# Parallel_CS_V4.net
KiCad netlist of a schematic drawn in EAGLE
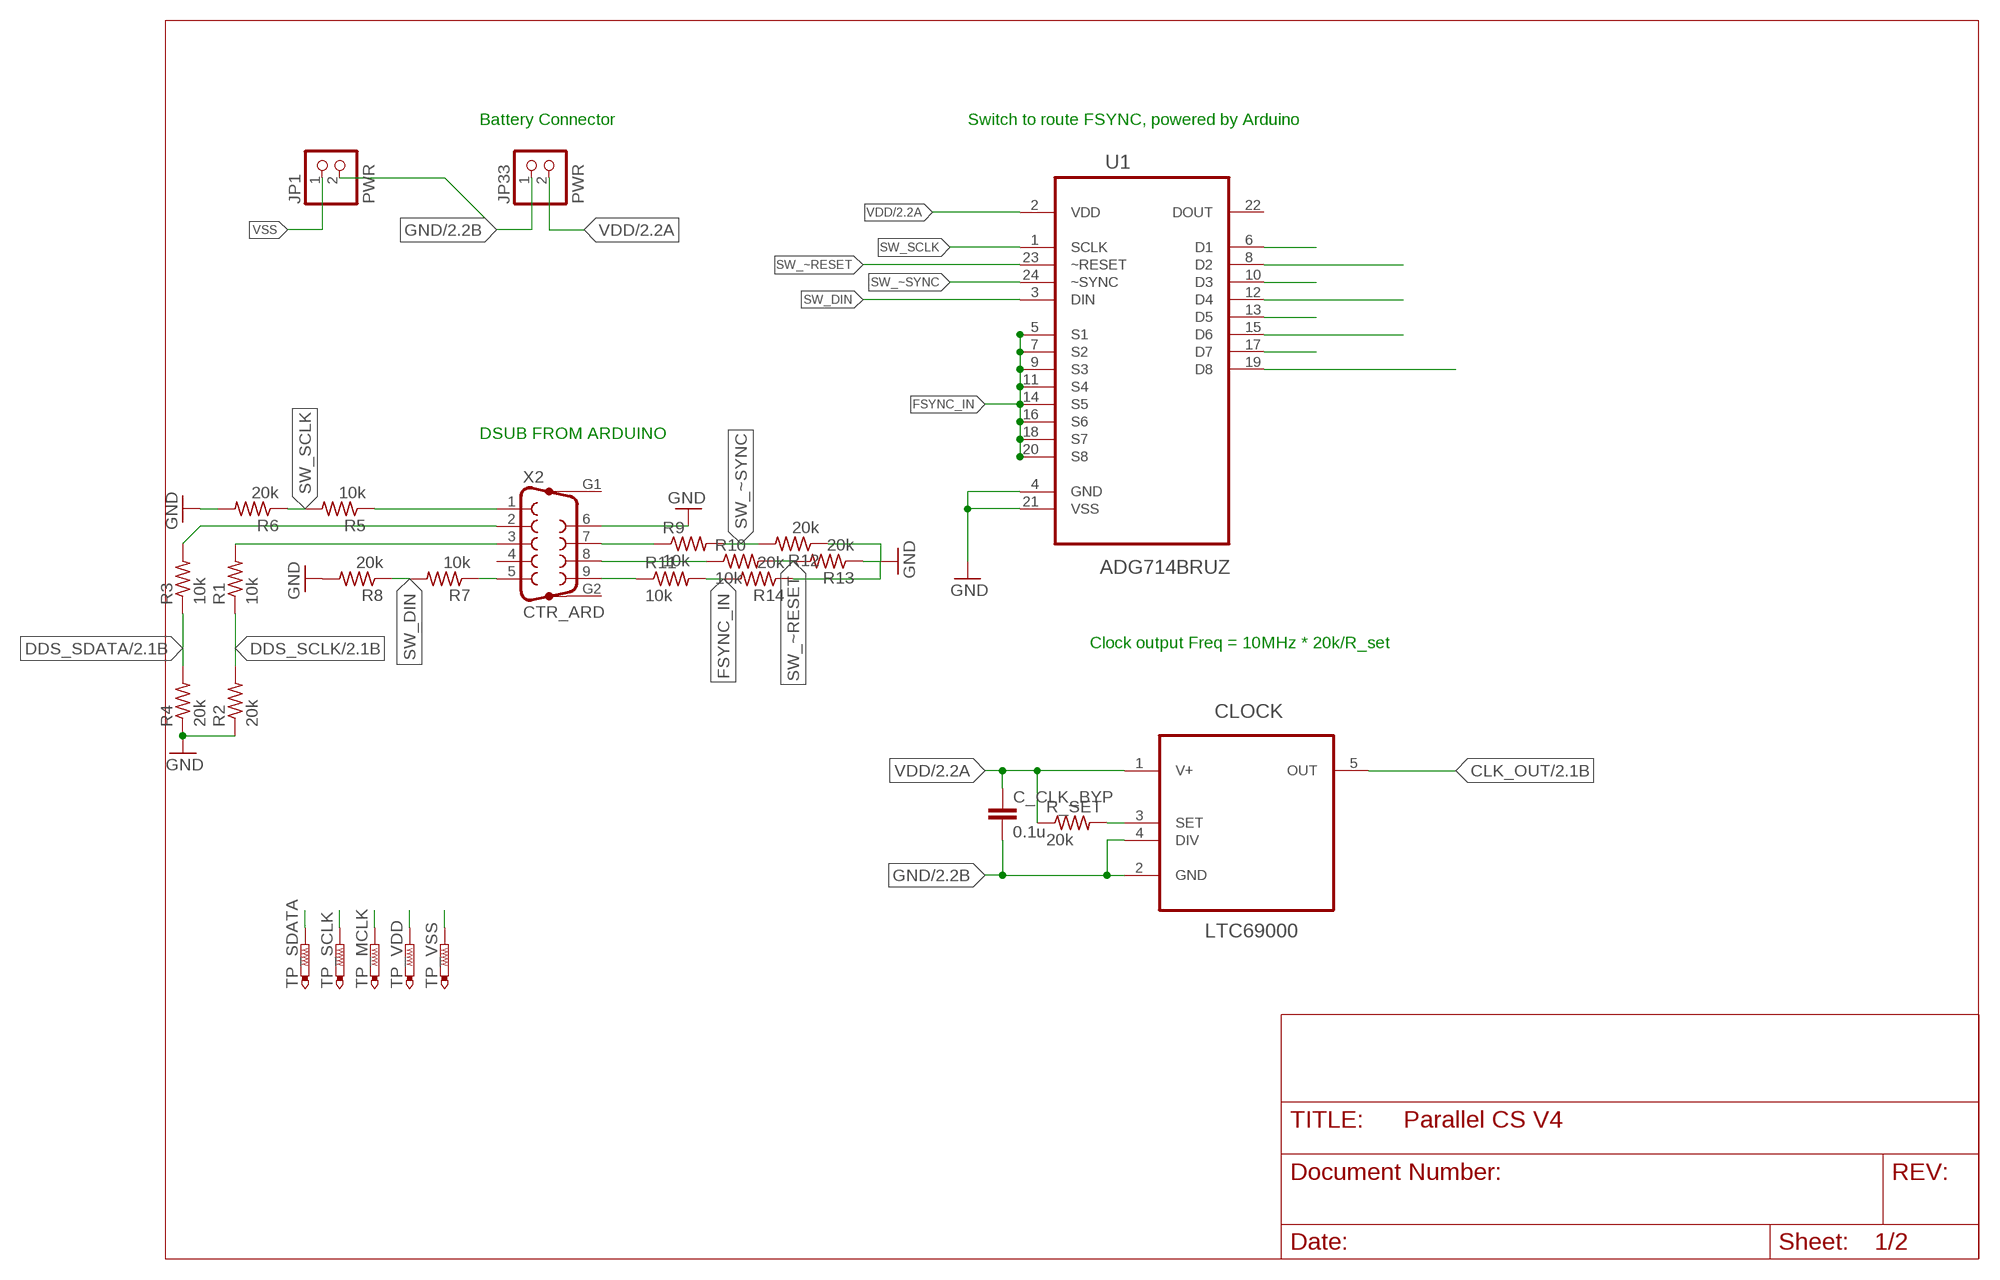
[diagram p0: schematic, sheet 1]
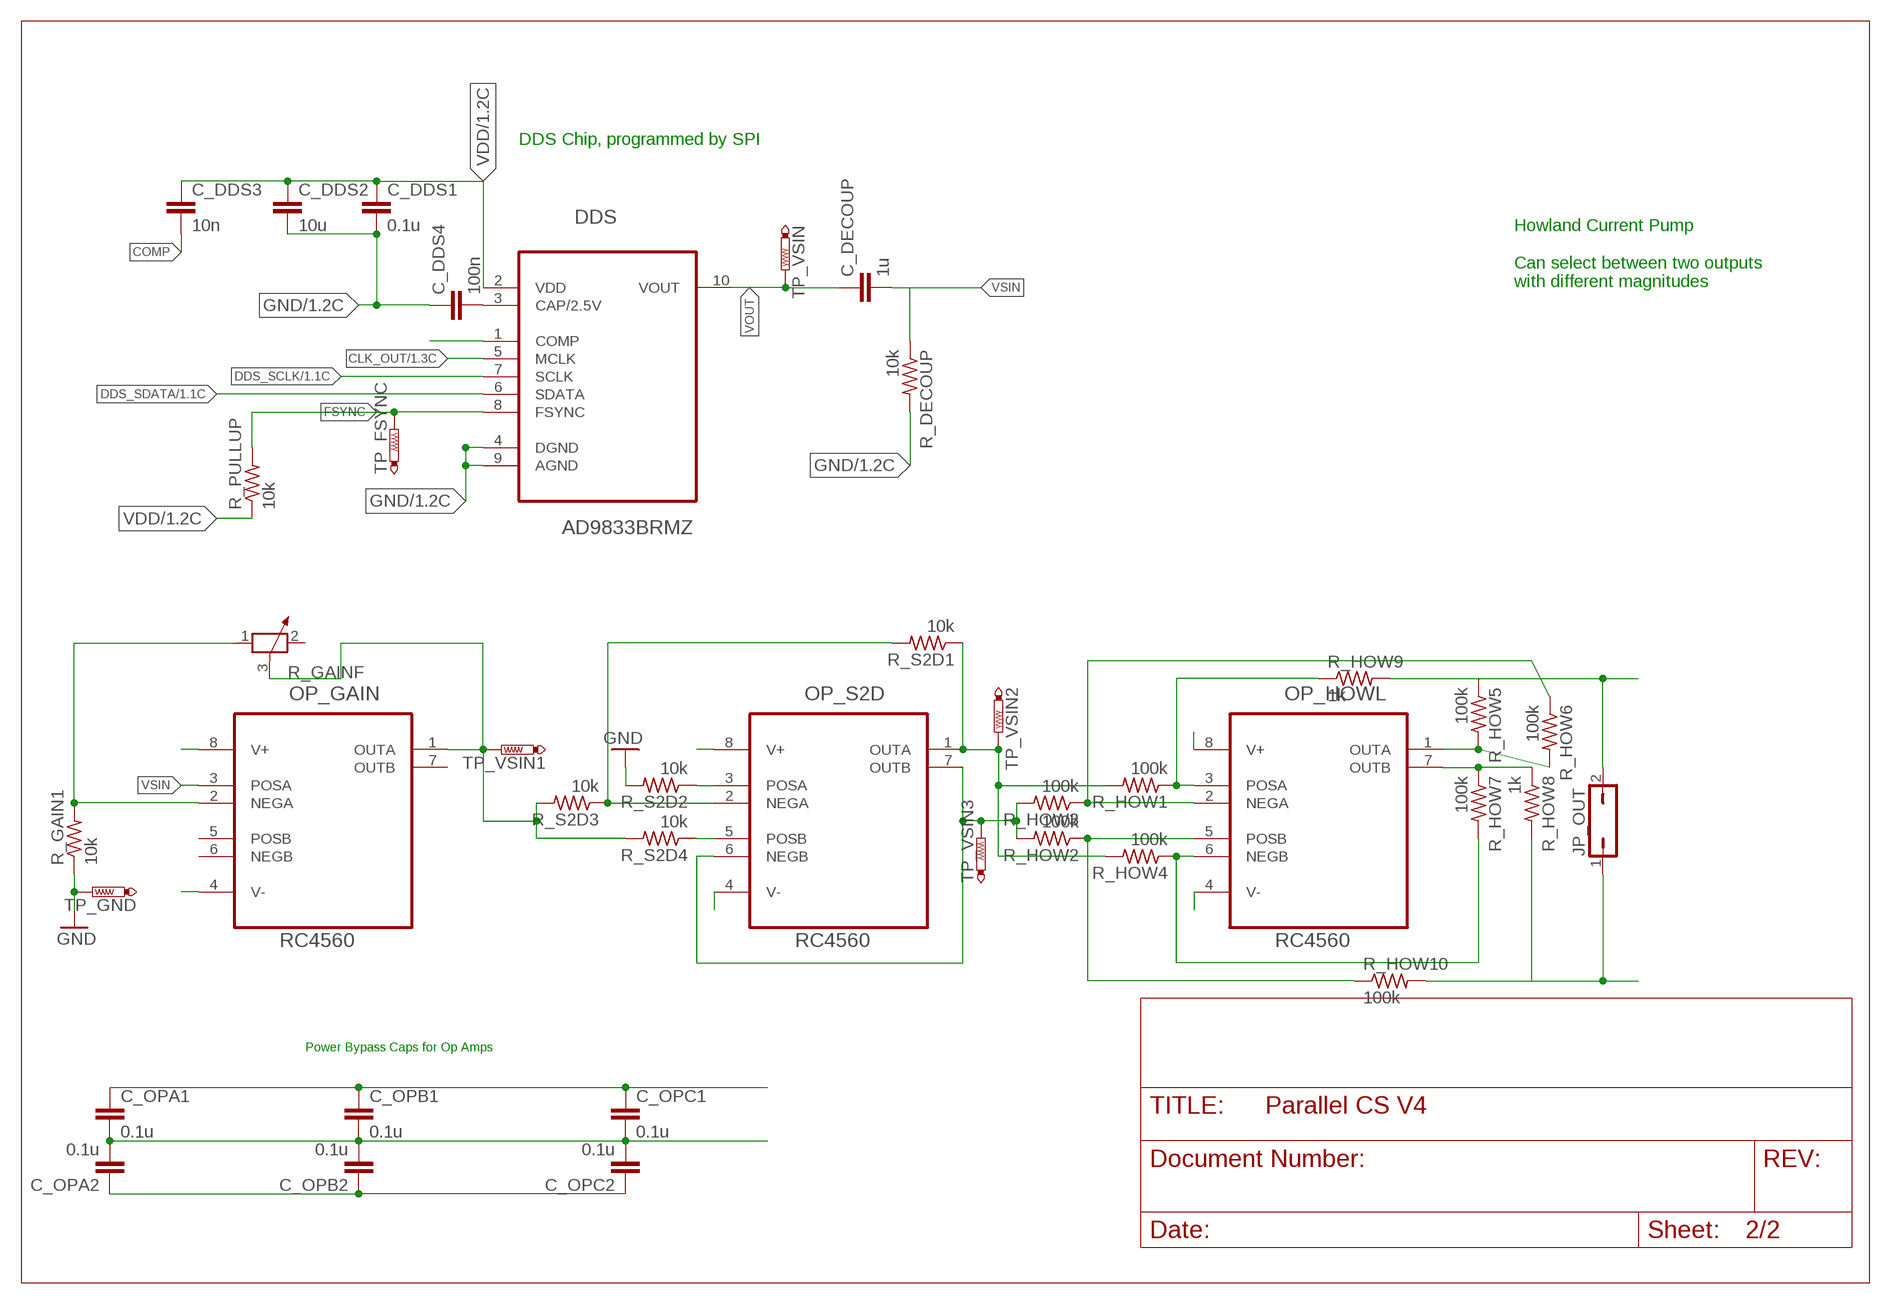
[diagram p1: schematic, sheet 2]

(export (version "E")
  (design (tool "Eeschema 10.0.6"))
  (components
    (comp (ref "C_DDS1")
      (value "0.1u")
      (footprint "eagle-import:C0805")
      (libsource (lib "eagle-import") (part "C-EUC0805"))
    )
    (comp (ref "C_DDS2")
      (value "10u")
      (footprint "eagle-import:C0805")
      (libsource (lib "eagle-import") (part "C-EUC0805"))
    )
    (comp (ref "C_DDS3")
      (value "10n")
      (footprint "eagle-import:C0805")
      (libsource (lib "eagle-import") (part "C-EUC0805"))
    )
    (comp (ref "C_DDS4")
      (value "100n")
      (footprint "eagle-import:C0805")
      (libsource (lib "eagle-import") (part "C-EUC0805"))
    )
    (comp (ref "C_DECOUP")
      (value "1u")
      (footprint "eagle-import:C0805")
      (libsource (lib "eagle-import") (part "C-EUC0805"))
    )
    (comp (ref "C_OPA1")
      (value "0.1u")
      (footprint "eagle-import:C0805")
      (libsource (lib "eagle-import") (part "C-EUC0805"))
    )
    (comp (ref "C_OPA2")
      (value "0.1u")
      (footprint "eagle-import:C0805")
      (libsource (lib "eagle-import") (part "C-EUC0805"))
    )
    (comp (ref "C_OPB1")
      (value "0.1u")
      (footprint "eagle-import:C0805")
      (libsource (lib "eagle-import") (part "C-EUC0805"))
    )
    (comp (ref "C_OPB2")
      (value "0.1u")
      (footprint "eagle-import:C0805")
      (libsource (lib "eagle-import") (part "C-EUC0805"))
    )
    (comp (ref "C_OPC1")
      (value "0.1u")
      (footprint "eagle-import:C0805")
      (libsource (lib "eagle-import") (part "C-EUC0805"))
    )
    (comp (ref "C_OPC2")
      (value "0.1u")
      (footprint "eagle-import:C0805")
      (libsource (lib "eagle-import") (part "C-EUC0805"))
    )
    (comp (ref "DDS")
      (value "AD9833BRMZ")
      (footprint "eagle-import:SOP50P490X110-10N")
      (libsource (lib "eagle-import") (part "AD9833BRMZ"))
    )
    (comp (ref "JP_OUT")
      (value "JP1Q")
      (footprint "eagle-import:JP1")
      (libsource (lib "eagle-import") (part "JP1Q"))
    )
    (comp (ref "OP_GAIN")
      (value "RC4560")
      (footprint "eagle-import:DIL08")
      (libsource (lib "eagle-import") (part "RC4560"))
    )
    (comp (ref "OP_HOWL")
      (value "RC4560")
      (footprint "eagle-import:DIL08")
      (libsource (lib "eagle-import") (part "RC4560"))
    )
    (comp (ref "OP_S2D")
      (value "RC4560")
      (footprint "eagle-import:DIL08")
      (libsource (lib "eagle-import") (part "RC4560"))
    )
    (comp (ref "R_DECOUP")
      (value "10k")
      (footprint "eagle-import:R0805")
      (libsource (lib "eagle-import") (part "R-US_R0805"))
    )
    (comp (ref "R_GAIN1")
      (value "10k")
      (footprint "eagle-import:R0805")
      (libsource (lib "eagle-import") (part "R-US_R0805"))
    )
    (comp (ref "R_GAINF")
      (value "POTENTIOMETER_PT-10")
      (footprint "eagle-import:PT-10")
      (libsource (lib "eagle-import") (part "POTENTIOMETER_PT-10"))
    )
    (comp (ref "R_HOW1")
      (value "100k")
      (footprint "eagle-import:R0805")
      (libsource (lib "eagle-import") (part "R-US_R0805"))
    )
    (comp (ref "R_HOW2")
      (value "100k")
      (footprint "eagle-import:R0805")
      (libsource (lib "eagle-import") (part "R-US_R0805"))
    )
    (comp (ref "R_HOW3")
      (value "100k")
      (footprint "eagle-import:R0805")
      (libsource (lib "eagle-import") (part "R-US_R0805"))
    )
    (comp (ref "R_HOW4")
      (value "100k")
      (footprint "eagle-import:R0805")
      (libsource (lib "eagle-import") (part "R-US_R0805"))
    )
    (comp (ref "R_HOW5")
      (value "100k")
      (footprint "eagle-import:R0805")
      (libsource (lib "eagle-import") (part "R-US_R0805"))
    )
    (comp (ref "R_HOW6")
      (value "100k")
      (footprint "eagle-import:R0805")
      (libsource (lib "eagle-import") (part "R-US_R0805"))
    )
    (comp (ref "R_HOW7")
      (value "100k")
      (footprint "eagle-import:R0805")
      (libsource (lib "eagle-import") (part "R-US_R0805"))
    )
    (comp (ref "R_HOW8")
      (value "1k")
      (footprint "eagle-import:R0805")
      (libsource (lib "eagle-import") (part "R-US_R0805"))
    )
    (comp (ref "R_HOW9")
      (value "1k")
      (footprint "eagle-import:R0805")
      (libsource (lib "eagle-import") (part "R-US_R0805"))
    )
    (comp (ref "R_HOW10")
      (value "100k")
      (footprint "eagle-import:R0805")
      (libsource (lib "eagle-import") (part "R-US_R0805"))
    )
    (comp (ref "R_PULLUP")
      (value "10k")
      (footprint "eagle-import:R0805")
      (libsource (lib "eagle-import") (part "R-US_R0805"))
    )
    (comp (ref "R_S2D1")
      (value "10k")
      (footprint "eagle-import:R0805")
      (libsource (lib "eagle-import") (part "R-US_R0805"))
    )
    (comp (ref "R_S2D2")
      (value "10k")
      (footprint "eagle-import:R0805")
      (libsource (lib "eagle-import") (part "R-US_R0805"))
    )
    (comp (ref "R_S2D3")
      (value "10k")
      (footprint "eagle-import:R0805")
      (libsource (lib "eagle-import") (part "R-US_R0805"))
    )
    (comp (ref "R_S2D4")
      (value "10k")
      (footprint "eagle-import:R0805")
      (libsource (lib "eagle-import") (part "R-US_R0805"))
    )
    (comp (ref "TP_FSYNC")
      (value "PTR1PAD1-13")
      (footprint "eagle-import:P1-13")
      (libsource (lib "eagle-import") (part "PTR1PAD1-13"))
    )
    (comp (ref "TP_GND")
      (value "PTR1PAD1-13")
      (footprint "eagle-import:P1-13")
      (libsource (lib "eagle-import") (part "PTR1PAD1-13"))
    )
    (comp (ref "TP_VSIN")
      (value "PTR1PAD1-13")
      (footprint "eagle-import:P1-13")
      (libsource (lib "eagle-import") (part "PTR1PAD1-13"))
    )
    (comp (ref "TP_VSIN1")
      (value "PTR1PAD1-13")
      (footprint "eagle-import:P1-13")
      (libsource (lib "eagle-import") (part "PTR1PAD1-13"))
    )
    (comp (ref "TP_VSIN2")
      (value "PTR1PAD1-13")
      (footprint "eagle-import:P1-13")
      (libsource (lib "eagle-import") (part "PTR1PAD1-13"))
    )
    (comp (ref "TP_VSIN3")
      (value "PTR1PAD1-13")
      (footprint "eagle-import:P1-13")
      (libsource (lib "eagle-import") (part "PTR1PAD1-13"))
    )
    (comp (ref "CLOCK")
      (value "LTC69000")
      (footprint "eagle-import:SOT23-5L")
      (libsource (lib "eagle-import") (part "LTC69000"))
    )
    (comp (ref "C_CLK_BYP")
      (value "0.1u")
      (footprint "eagle-import:C0805")
      (libsource (lib "eagle-import") (part "C-EUC0805"))
    )
    (comp (ref "JP1")
      (value "PWR")
      (footprint "eagle-import:1X02")
      (libsource (lib "eagle-import") (part "PINHD-1X2"))
    )
    (comp (ref "JP33")
      (value "PWR")
      (footprint "eagle-import:1X02")
      (libsource (lib "eagle-import") (part "PINHD-1X2"))
    )
    (comp (ref "R1")
      (value "10k")
      (footprint "eagle-import:R0805")
      (libsource (lib "eagle-import") (part "resistor_R-US_R0805"))
    )
    (comp (ref "R2")
      (value "20k")
      (footprint "eagle-import:R0603")
      (libsource (lib "eagle-import") (part "resistor_R-US_R0603"))
    )
    (comp (ref "R3")
      (value "10k")
      (footprint "eagle-import:R0805")
      (libsource (lib "eagle-import") (part "resistor_R-US_R0805"))
    )
    (comp (ref "R4")
      (value "20k")
      (footprint "eagle-import:R0603")
      (libsource (lib "eagle-import") (part "resistor_R-US_R0603"))
    )
    (comp (ref "R5")
      (value "10k")
      (footprint "eagle-import:R0805")
      (libsource (lib "eagle-import") (part "resistor_R-US_R0805"))
    )
    (comp (ref "R6")
      (value "20k")
      (footprint "eagle-import:R0603")
      (libsource (lib "eagle-import") (part "resistor_R-US_R0603"))
    )
    (comp (ref "R7")
      (value "10k")
      (footprint "eagle-import:R0805")
      (libsource (lib "eagle-import") (part "resistor_R-US_R0805"))
    )
    (comp (ref "R8")
      (value "20k")
      (footprint "eagle-import:R0603")
      (libsource (lib "eagle-import") (part "resistor_R-US_R0603"))
    )
    (comp (ref "R9")
      (value "10k")
      (footprint "eagle-import:R0805")
      (libsource (lib "eagle-import") (part "resistor_R-US_R0805"))
    )
    (comp (ref "R10")
      (value "10k")
      (footprint "eagle-import:R0805")
      (libsource (lib "eagle-import") (part "resistor_R-US_R0805"))
    )
    (comp (ref "R11")
      (value "10k")
      (footprint "eagle-import:R0805")
      (libsource (lib "eagle-import") (part "resistor_R-US_R0805"))
    )
    (comp (ref "R12")
      (value "20k")
      (footprint "eagle-import:R0603")
      (libsource (lib "eagle-import") (part "resistor_R-US_R0603"))
    )
    (comp (ref "R13")
      (value "20k")
      (footprint "eagle-import:R0603")
      (libsource (lib "eagle-import") (part "resistor_R-US_R0603"))
    )
    (comp (ref "R14")
      (value "20k")
      (footprint "eagle-import:R0603")
      (libsource (lib "eagle-import") (part "resistor_R-US_R0603"))
    )
    (comp (ref "R_SET")
      (value "20k")
      (footprint "eagle-import:R0603")
      (libsource (lib "eagle-import") (part "resistor_R-US_R0603"))
    )
    (comp (ref "TP_MCLK")
      (value "PTR1PAD1-13")
      (footprint "eagle-import:P1-13")
      (libsource (lib "eagle-import") (part "PTR1PAD1-13"))
    )
    (comp (ref "TP_SCLK")
      (value "PTR1PAD1-13")
      (footprint "eagle-import:P1-13")
      (libsource (lib "eagle-import") (part "PTR1PAD1-13"))
    )
    (comp (ref "TP_SDATA")
      (value "PTR1PAD1-13")
      (footprint "eagle-import:P1-13")
      (libsource (lib "eagle-import") (part "PTR1PAD1-13"))
    )
    (comp (ref "TP_VDD")
      (value "PTR1PAD1-13")
      (footprint "eagle-import:P1-13")
      (libsource (lib "eagle-import") (part "PTR1PAD1-13"))
    )
    (comp (ref "TP_VSS")
      (value "PTR1PAD1-13")
      (footprint "eagle-import:P1-13")
      (libsource (lib "eagle-import") (part "PTR1PAD1-13"))
    )
    (comp (ref "U1")
      (value "ADG714BRUZ")
      (footprint "eagle-import:SOP65P640X120-24N")
      (libsource (lib "eagle-import") (part "ADG714BRUZ"))
    )
    (comp (ref "X2")
      (value "CTR_ARD")
      (footprint "eagle-import:F09HP")
      (libsource (lib "eagle-import") (part "F09HP"))
    )
  )
  (nets
    (net (code "1") (name "CLK_OUT") (class "Default")
      (node (ref "CLOCK") (pin "5") (pinfunction "OUT_5") (pintype "output"))
      (node (ref "DDS") (pin "5") (pinfunction "MCLK_5") (pintype "input"))
      (node (ref "TP_MCLK") (pin "TP") (pinfunction "TP_TP") (pintype "input"))
    )
    (net (code "2") (name "COMP") (class "Default")
      (node (ref "C_DDS3") (pin "2") (pinfunction "2_2") (pintype "passive"))
      (node (ref "DDS") (pin "1") (pinfunction "COMP_1") (pintype "passive"))
    )
    (net (code "3") (name "DDS_SCLK") (class "Default")
      (node (ref "DDS") (pin "7") (pinfunction "SCLK_7") (pintype "input"))
      (node (ref "R1") (pin "1") (pinfunction "1_1") (pintype "passive"))
      (node (ref "R2") (pin "2") (pinfunction "2_2") (pintype "passive"))
      (node (ref "TP_SCLK") (pin "TP") (pinfunction "TP_TP") (pintype "input"))
    )
    (net (code "4") (name "DDS_SDATA") (class "Default")
      (node (ref "DDS") (pin "6") (pinfunction "SDATA_6") (pintype "input"))
      (node (ref "R3") (pin "1") (pinfunction "1_1") (pintype "passive"))
      (node (ref "R4") (pin "2") (pinfunction "2_2") (pintype "passive"))
      (node (ref "TP_SDATA") (pin "TP") (pinfunction "TP_TP") (pintype "input"))
    )
    (net (code "5") (name "FSYNC") (class "Default")
      (node (ref "DDS") (pin "8") (pinfunction "FSYNC_8") (pintype "input"))
      (node (ref "R_PULLUP") (pin "2") (pinfunction "2_2") (pintype "passive"))
      (node (ref "TP_FSYNC") (pin "TP") (pinfunction "TP_TP") (pintype "input"))
    )
    (net (code "6") (name "FSYNC_IN") (class "Default")
      (node (ref "R11") (pin "2") (pinfunction "2_2") (pintype "passive"))
      (node (ref "R14") (pin "2") (pinfunction "2_2") (pintype "passive"))
      (node (ref "U1") (pin "11") (pinfunction "S4_11") (pintype "bidirectional"))
      (node (ref "U1") (pin "14") (pinfunction "S5_14") (pintype "bidirectional"))
      (node (ref "U1") (pin "16") (pinfunction "S6_16") (pintype "bidirectional"))
      (node (ref "U1") (pin "18") (pinfunction "S7_18") (pintype "bidirectional"))
      (node (ref "U1") (pin "20") (pinfunction "S8_20") (pintype "bidirectional"))
      (node (ref "U1") (pin "5") (pinfunction "S1_5") (pintype "bidirectional"))
      (node (ref "U1") (pin "7") (pinfunction "S2_7") (pintype "bidirectional"))
      (node (ref "U1") (pin "9") (pinfunction "S3_9") (pintype "bidirectional"))
    )
    (net (code "7") (name "GND") (class "Default")
      (node (ref "CLOCK") (pin "2") (pinfunction "GND_2") (pintype "passive"))
      (node (ref "CLOCK") (pin "4") (pinfunction "DIV_4") (pintype "input"))
      (node (ref "C_CLK_BYP") (pin "2") (pinfunction "2_2") (pintype "passive"))
      (node (ref "C_DDS1") (pin "2") (pinfunction "2_2") (pintype "passive"))
      (node (ref "C_DDS2") (pin "2") (pinfunction "2_2") (pintype "passive"))
      (node (ref "C_DDS4") (pin "1") (pinfunction "1_1") (pintype "passive"))
      (node (ref "C_OPA1") (pin "2") (pinfunction "2_2") (pintype "passive"))
      (node (ref "C_OPA2") (pin "2") (pinfunction "2_2") (pintype "passive"))
      (node (ref "C_OPB1") (pin "2") (pinfunction "2_2") (pintype "passive"))
      (node (ref "C_OPB2") (pin "2") (pinfunction "2_2") (pintype "passive"))
      (node (ref "C_OPC1") (pin "2") (pinfunction "2_2") (pintype "passive"))
      (node (ref "C_OPC2") (pin "2") (pinfunction "2_2") (pintype "passive"))
      (node (ref "DDS") (pin "4") (pinfunction "DGND_4") (pintype "passive"))
      (node (ref "DDS") (pin "9") (pinfunction "AGND_9") (pintype "passive"))
      (node (ref "JP1") (pin "2") (pinfunction "2_2") (pintype "passive"))
      (node (ref "JP33") (pin "1") (pinfunction "1_1") (pintype "passive"))
      (node (ref "R12") (pin "1") (pinfunction "1_1") (pintype "passive"))
      (node (ref "R13") (pin "1") (pinfunction "1_1") (pintype "passive"))
      (node (ref "R14") (pin "1") (pinfunction "1_1") (pintype "passive"))
      (node (ref "R2") (pin "1") (pinfunction "1_1") (pintype "passive"))
      (node (ref "R4") (pin "1") (pinfunction "1_1") (pintype "passive"))
      (node (ref "R6") (pin "2") (pinfunction "2_2") (pintype "passive"))
      (node (ref "R8") (pin "2") (pinfunction "2_2") (pintype "passive"))
      (node (ref "R_DECOUP") (pin "2") (pinfunction "2_2") (pintype "passive"))
      (node (ref "R_GAIN1") (pin "1") (pinfunction "1_1") (pintype "passive"))
      (node (ref "R_S2D2") (pin "2") (pinfunction "2_2") (pintype "passive"))
      (node (ref "TP_GND") (pin "TP") (pinfunction "TP_TP") (pintype "input"))
      (node (ref "U1") (pin "21") (pinfunction "VSS_21") (pintype "power_in"))
      (node (ref "U1") (pin "4") (pinfunction "GND_4") (pintype "passive"))
      (node (ref "X2") (pin "6") (pinfunction "6_6") (pintype "passive"))
    )
    (net (code "8") (name "Net-(CLOCK-SET)") (class "Default")
      (node (ref "CLOCK") (pin "3") (pinfunction "SET_3") (pintype "input"))
      (node (ref "R_SET") (pin "2") (pinfunction "2_2") (pintype "passive"))
    )
    (net (code "9") (name "Net-(DDS-CAP{slash}2.5V)") (class "Default")
      (node (ref "C_DDS4") (pin "2") (pinfunction "2_2") (pintype "passive"))
      (node (ref "DDS") (pin "3") (pinfunction "CAP/2.5V_3") (pintype "passive"))
    )
    (net (code "10") (name "Net-(JP_OUT-Pad1)") (class "Default")
      (node (ref "JP_OUT") (pin "1") (pinfunction "1_1") (pintype "passive"))
      (node (ref "R_HOW10") (pin "2") (pinfunction "2_2") (pintype "passive"))
      (node (ref "R_HOW8") (pin "2") (pinfunction "2_2") (pintype "passive"))
    )
    (net (code "11") (name "Net-(JP_OUT-Pad2)") (class "Default")
      (node (ref "JP_OUT") (pin "2") (pinfunction "2_2") (pintype "passive"))
      (node (ref "R_HOW5") (pin "1") (pinfunction "1_1") (pintype "passive"))
      (node (ref "R_HOW9") (pin "2") (pinfunction "2_2") (pintype "passive"))
    )
    (net (code "12") (name "Net-(OP_GAIN-NEGA)") (class "Default")
      (node (ref "OP_GAIN") (pin "2") (pinfunction "NEGA_2") (pintype "input"))
      (node (ref "R_GAIN1") (pin "2") (pinfunction "2_2") (pintype "passive"))
      (node (ref "R_GAINF") (pin "1") (pinfunction "1_1") (pintype "passive"))
    )
    (net (code "13") (name "Net-(OP_GAIN-OUTA)") (class "Default")
      (node (ref "OP_GAIN") (pin "1") (pinfunction "OUTA_1") (pintype "output"))
      (node (ref "R_GAINF") (pin "3") (pinfunction "3_3") (pintype "passive"))
      (node (ref "R_S2D3") (pin "2") (pinfunction "2_2") (pintype "passive"))
      (node (ref "R_S2D4") (pin "2") (pinfunction "2_2") (pintype "passive"))
      (node (ref "TP_VSIN1") (pin "TP") (pinfunction "TP_TP") (pintype "input"))
    )
    (net (code "14") (name "Net-(OP_HOWL-NEGA)") (class "Default")
      (node (ref "OP_HOWL") (pin "2") (pinfunction "NEGA_2") (pintype "input"))
      (node (ref "R_HOW3") (pin "1") (pinfunction "1_1") (pintype "passive"))
      (node (ref "R_HOW6") (pin "1") (pinfunction "1_1") (pintype "passive"))
    )
    (net (code "15") (name "Net-(OP_HOWL-NEGB)") (class "Default")
      (node (ref "OP_HOWL") (pin "6") (pinfunction "NEGB_6") (pintype "input"))
      (node (ref "R_HOW4") (pin "1") (pinfunction "1_1") (pintype "passive"))
      (node (ref "R_HOW7") (pin "2") (pinfunction "2_2") (pintype "passive"))
    )
    (net (code "16") (name "Net-(OP_HOWL-OUTA)") (class "Default")
      (node (ref "OP_HOWL") (pin "1") (pinfunction "OUTA_1") (pintype "output"))
      (node (ref "R_HOW5") (pin "2") (pinfunction "2_2") (pintype "passive"))
      (node (ref "R_HOW6") (pin "2") (pinfunction "2_2") (pintype "passive"))
    )
    (net (code "17") (name "Net-(OP_HOWL-OUTB)") (class "Default")
      (node (ref "OP_HOWL") (pin "7") (pinfunction "OUTB_7") (pintype "output"))
      (node (ref "R_HOW7") (pin "1") (pinfunction "1_1") (pintype "passive"))
      (node (ref "R_HOW8") (pin "1") (pinfunction "1_1") (pintype "passive"))
    )
    (net (code "18") (name "Net-(OP_HOWL-POSA)") (class "Default")
      (node (ref "OP_HOWL") (pin "3") (pinfunction "POSA_3") (pintype "input"))
      (node (ref "R_HOW1") (pin "1") (pinfunction "1_1") (pintype "passive"))
      (node (ref "R_HOW9") (pin "1") (pinfunction "1_1") (pintype "passive"))
    )
    (net (code "19") (name "Net-(OP_HOWL-POSB)") (class "Default")
      (node (ref "OP_HOWL") (pin "5") (pinfunction "POSB_5") (pintype "input"))
      (node (ref "R_HOW10") (pin "1") (pinfunction "1_1") (pintype "passive"))
      (node (ref "R_HOW2") (pin "1") (pinfunction "1_1") (pintype "passive"))
    )
    (net (code "20") (name "Net-(OP_S2D-NEGA)") (class "Default")
      (node (ref "OP_S2D") (pin "2") (pinfunction "NEGA_2") (pintype "input"))
      (node (ref "R_S2D1") (pin "2") (pinfunction "2_2") (pintype "passive"))
      (node (ref "R_S2D3") (pin "1") (pinfunction "1_1") (pintype "passive"))
    )
    (net (code "21") (name "Net-(OP_S2D-NEGB)") (class "Default")
      (node (ref "OP_S2D") (pin "6") (pinfunction "NEGB_6") (pintype "input"))
      (node (ref "OP_S2D") (pin "7") (pinfunction "OUTB_7") (pintype "output"))
      (node (ref "R_HOW2") (pin "2") (pinfunction "2_2") (pintype "passive"))
      (node (ref "R_HOW3") (pin "2") (pinfunction "2_2") (pintype "passive"))
      (node (ref "TP_VSIN3") (pin "TP") (pinfunction "TP_TP") (pintype "input"))
    )
    (net (code "22") (name "Net-(OP_S2D-OUTA)") (class "Default")
      (node (ref "OP_S2D") (pin "1") (pinfunction "OUTA_1") (pintype "output"))
      (node (ref "R_HOW1") (pin "2") (pinfunction "2_2") (pintype "passive"))
      (node (ref "R_HOW4") (pin "2") (pinfunction "2_2") (pintype "passive"))
      (node (ref "R_S2D1") (pin "1") (pinfunction "1_1") (pintype "passive"))
      (node (ref "TP_VSIN2") (pin "TP") (pinfunction "TP_TP") (pintype "input"))
    )
    (net (code "23") (name "Net-(OP_S2D-POSA)") (class "Default")
      (node (ref "OP_S2D") (pin "3") (pinfunction "POSA_3") (pintype "input"))
      (node (ref "R_S2D2") (pin "1") (pinfunction "1_1") (pintype "passive"))
    )
    (net (code "24") (name "Net-(OP_S2D-POSB)") (class "Default")
      (node (ref "OP_S2D") (pin "5") (pinfunction "POSB_5") (pintype "input"))
      (node (ref "R_S2D4") (pin "1") (pinfunction "1_1") (pintype "passive"))
    )
    (net (code "25") (name "Net-(R1-Pad2)") (class "Default")
      (node (ref "R1") (pin "2") (pinfunction "2_2") (pintype "passive"))
      (node (ref "X2") (pin "3") (pinfunction "3_3") (pintype "passive"))
    )
    (net (code "26") (name "Net-(R3-Pad2)") (class "Default")
      (node (ref "R3") (pin "2") (pinfunction "2_2") (pintype "passive"))
      (node (ref "X2") (pin "2") (pinfunction "2_2") (pintype "passive"))
    )
    (net (code "27") (name "Net-(R5-Pad1)") (class "Default")
      (node (ref "R5") (pin "1") (pinfunction "1_1") (pintype "passive"))
      (node (ref "X2") (pin "1") (pinfunction "1_1") (pintype "passive"))
    )
    (net (code "28") (name "Net-(R7-Pad1)") (class "Default")
      (node (ref "R7") (pin "1") (pinfunction "1_1") (pintype "passive"))
      (node (ref "X2") (pin "5") (pinfunction "5_5") (pintype "passive"))
    )
    (net (code "29") (name "Net-(R9-Pad1)") (class "Default")
      (node (ref "R9") (pin "1") (pinfunction "1_1") (pintype "passive"))
      (node (ref "X2") (pin "7") (pinfunction "7_7") (pintype "passive"))
    )
    (net (code "30") (name "Net-(R10-Pad1)") (class "Default")
      (node (ref "R10") (pin "1") (pinfunction "1_1") (pintype "passive"))
      (node (ref "X2") (pin "8") (pinfunction "8_8") (pintype "passive"))
    )
    (net (code "31") (name "Net-(R11-Pad1)") (class "Default")
      (node (ref "R11") (pin "1") (pinfunction "1_1") (pintype "passive"))
      (node (ref "X2") (pin "9") (pinfunction "9_9") (pintype "passive"))
    )
    (net (code "32") (name "SW_DIN") (class "Default")
      (node (ref "R7") (pin "2") (pinfunction "2_2") (pintype "passive"))
      (node (ref "R8") (pin "1") (pinfunction "1_1") (pintype "passive"))
      (node (ref "U1") (pin "3") (pinfunction "DIN_3") (pintype "input"))
    )
    (net (code "33") (name "SW_SCLK") (class "Default")
      (node (ref "R5") (pin "2") (pinfunction "2_2") (pintype "passive"))
      (node (ref "R6") (pin "1") (pinfunction "1_1") (pintype "passive"))
      (node (ref "U1") (pin "1") (pinfunction "SCLK_1") (pintype "input"))
    )
    (net (code "34") (name "SW_~{RESET}") (class "Default")
      (node (ref "R10") (pin "2") (pinfunction "2_2") (pintype "passive"))
      (node (ref "R13") (pin "2") (pinfunction "2_2") (pintype "passive"))
      (node (ref "U1") (pin "23") (pinfunction "~{RESET}_23") (pintype "input"))
    )
    (net (code "35") (name "SW_~{SYNC}") (class "Default")
      (node (ref "R12") (pin "2") (pinfunction "2_2") (pintype "passive"))
      (node (ref "R9") (pin "2") (pinfunction "2_2") (pintype "passive"))
      (node (ref "U1") (pin "24") (pinfunction "~{SYNC}_24") (pintype "input"))
    )
    (net (code "36") (name "VDD") (class "Default")
      (node (ref "CLOCK") (pin "1") (pinfunction "V+_1") (pintype "power_in"))
      (node (ref "C_CLK_BYP") (pin "1") (pinfunction "1_1") (pintype "passive"))
      (node (ref "C_DDS1") (pin "1") (pinfunction "1_1") (pintype "passive"))
      (node (ref "C_DDS2") (pin "1") (pinfunction "1_1") (pintype "passive"))
      (node (ref "C_DDS3") (pin "1") (pinfunction "1_1") (pintype "passive"))
      (node (ref "C_OPA1") (pin "1") (pinfunction "1_1") (pintype "passive"))
      (node (ref "C_OPB1") (pin "1") (pinfunction "1_1") (pintype "passive"))
      (node (ref "C_OPC1") (pin "1") (pinfunction "1_1") (pintype "passive"))
      (node (ref "DDS") (pin "2") (pinfunction "VDD_2") (pintype "power_in"))
      (node (ref "JP33") (pin "2") (pinfunction "2_2") (pintype "passive"))
      (node (ref "OP_GAIN") (pin "8") (pinfunction "V+_8") (pintype "power_in"))
      (node (ref "OP_HOWL") (pin "8") (pinfunction "V+_8") (pintype "power_in"))
      (node (ref "OP_S2D") (pin "8") (pinfunction "V+_8") (pintype "power_in"))
      (node (ref "R_PULLUP") (pin "1") (pinfunction "1_1") (pintype "passive"))
      (node (ref "R_SET") (pin "1") (pinfunction "1_1") (pintype "passive"))
      (node (ref "TP_VDD") (pin "TP") (pinfunction "TP_TP") (pintype "input"))
      (node (ref "U1") (pin "2") (pinfunction "VDD_2") (pintype "power_in"))
    )
    (net (code "37") (name "VOUT") (class "Default")
      (node (ref "C_DECOUP") (pin "1") (pinfunction "1_1") (pintype "passive"))
      (node (ref "DDS") (pin "10") (pinfunction "VOUT_10") (pintype "output"))
      (node (ref "TP_VSIN") (pin "TP") (pinfunction "TP_TP") (pintype "input"))
    )
    (net (code "38") (name "VSIN") (class "Default")
      (node (ref "C_DECOUP") (pin "2") (pinfunction "2_2") (pintype "passive"))
      (node (ref "OP_GAIN") (pin "3") (pinfunction "POSA_3") (pintype "input"))
      (node (ref "R_DECOUP") (pin "1") (pinfunction "1_1") (pintype "passive"))
    )
    (net (code "39") (name "VSS") (class "Default")
      (node (ref "C_OPA2") (pin "1") (pinfunction "1_1") (pintype "passive"))
      (node (ref "C_OPB2") (pin "1") (pinfunction "1_1") (pintype "passive"))
      (node (ref "C_OPC2") (pin "1") (pinfunction "1_1") (pintype "passive"))
      (node (ref "JP1") (pin "1") (pinfunction "1_1") (pintype "passive"))
      (node (ref "OP_GAIN") (pin "4") (pinfunction "V-_4") (pintype "power_in"))
      (node (ref "OP_HOWL") (pin "4") (pinfunction "V-_4") (pintype "power_in"))
      (node (ref "OP_S2D") (pin "4") (pinfunction "V-_4") (pintype "power_in"))
      (node (ref "TP_VSS") (pin "TP") (pinfunction "TP_TP") (pintype "input"))
    )
    (net (code "40") (name "unconnected-(OP_GAIN-NEGB-Pad6)") (class "Default")
      (node (ref "OP_GAIN") (pin "6") (pinfunction "NEGB_6") (pintype "input"))
    )
    (net (code "41") (name "unconnected-(OP_GAIN-OUTB-Pad7)") (class "Default")
      (node (ref "OP_GAIN") (pin "7") (pinfunction "OUTB_7") (pintype "output"))
    )
    (net (code "42") (name "unconnected-(OP_GAIN-POSB-Pad5)") (class "Default")
      (node (ref "OP_GAIN") (pin "5") (pinfunction "POSB_5") (pintype "input"))
    )
    (net (code "43") (name "unconnected-(R_GAINF-Pad2)") (class "Default")
      (node (ref "R_GAINF") (pin "2") (pinfunction "2_2") (pintype "passive"))
    )
    (net (code "44") (name "unconnected-(U1-D1-Pad6)") (class "Default")
      (node (ref "U1") (pin "6") (pinfunction "D1_6") (pintype "bidirectional"))
    )
    (net (code "45") (name "unconnected-(U1-D2-Pad8)") (class "Default")
      (node (ref "U1") (pin "8") (pinfunction "D2_8") (pintype "bidirectional"))
    )
    (net (code "46") (name "unconnected-(U1-D3-Pad10)") (class "Default")
      (node (ref "U1") (pin "10") (pinfunction "D3_10") (pintype "bidirectional"))
    )
    (net (code "47") (name "unconnected-(U1-D4-Pad12)") (class "Default")
      (node (ref "U1") (pin "12") (pinfunction "D4_12") (pintype "bidirectional"))
    )
    (net (code "48") (name "unconnected-(U1-D5-Pad13)") (class "Default")
      (node (ref "U1") (pin "13") (pinfunction "D5_13") (pintype "bidirectional"))
    )
    (net (code "49") (name "unconnected-(U1-D6-Pad15)") (class "Default")
      (node (ref "U1") (pin "15") (pinfunction "D6_15") (pintype "bidirectional"))
    )
    (net (code "50") (name "unconnected-(U1-D7-Pad17)") (class "Default")
      (node (ref "U1") (pin "17") (pinfunction "D7_17") (pintype "bidirectional"))
    )
    (net (code "51") (name "unconnected-(U1-D8-Pad19)") (class "Default")
      (node (ref "U1") (pin "19") (pinfunction "D8_19") (pintype "bidirectional"))
    )
    (net (code "52") (name "unconnected-(U1-DOUT-Pad22)") (class "Default")
      (node (ref "U1") (pin "22") (pinfunction "DOUT_22") (pintype "output"))
    )
    (net (code "53") (name "unconnected-(X2-Pad4)") (class "Default")
      (node (ref "X2") (pin "4") (pinfunction "4_4") (pintype "passive"))
    )
    (net (code "54") (name "unconnected-(X2-PadG1)") (class "Default")
      (node (ref "X2") (pin "G1") (pinfunction "G1_G1") (pintype "passive"))
    )
    (net (code "55") (name "unconnected-(X2-PadG2)") (class "Default")
      (node (ref "X2") (pin "G2") (pinfunction "G2_G2") (pintype "passive"))
    )
  )
)
